# RoverWing-V1_4.net
KiCad netlist of a schematic drawn in EAGLE
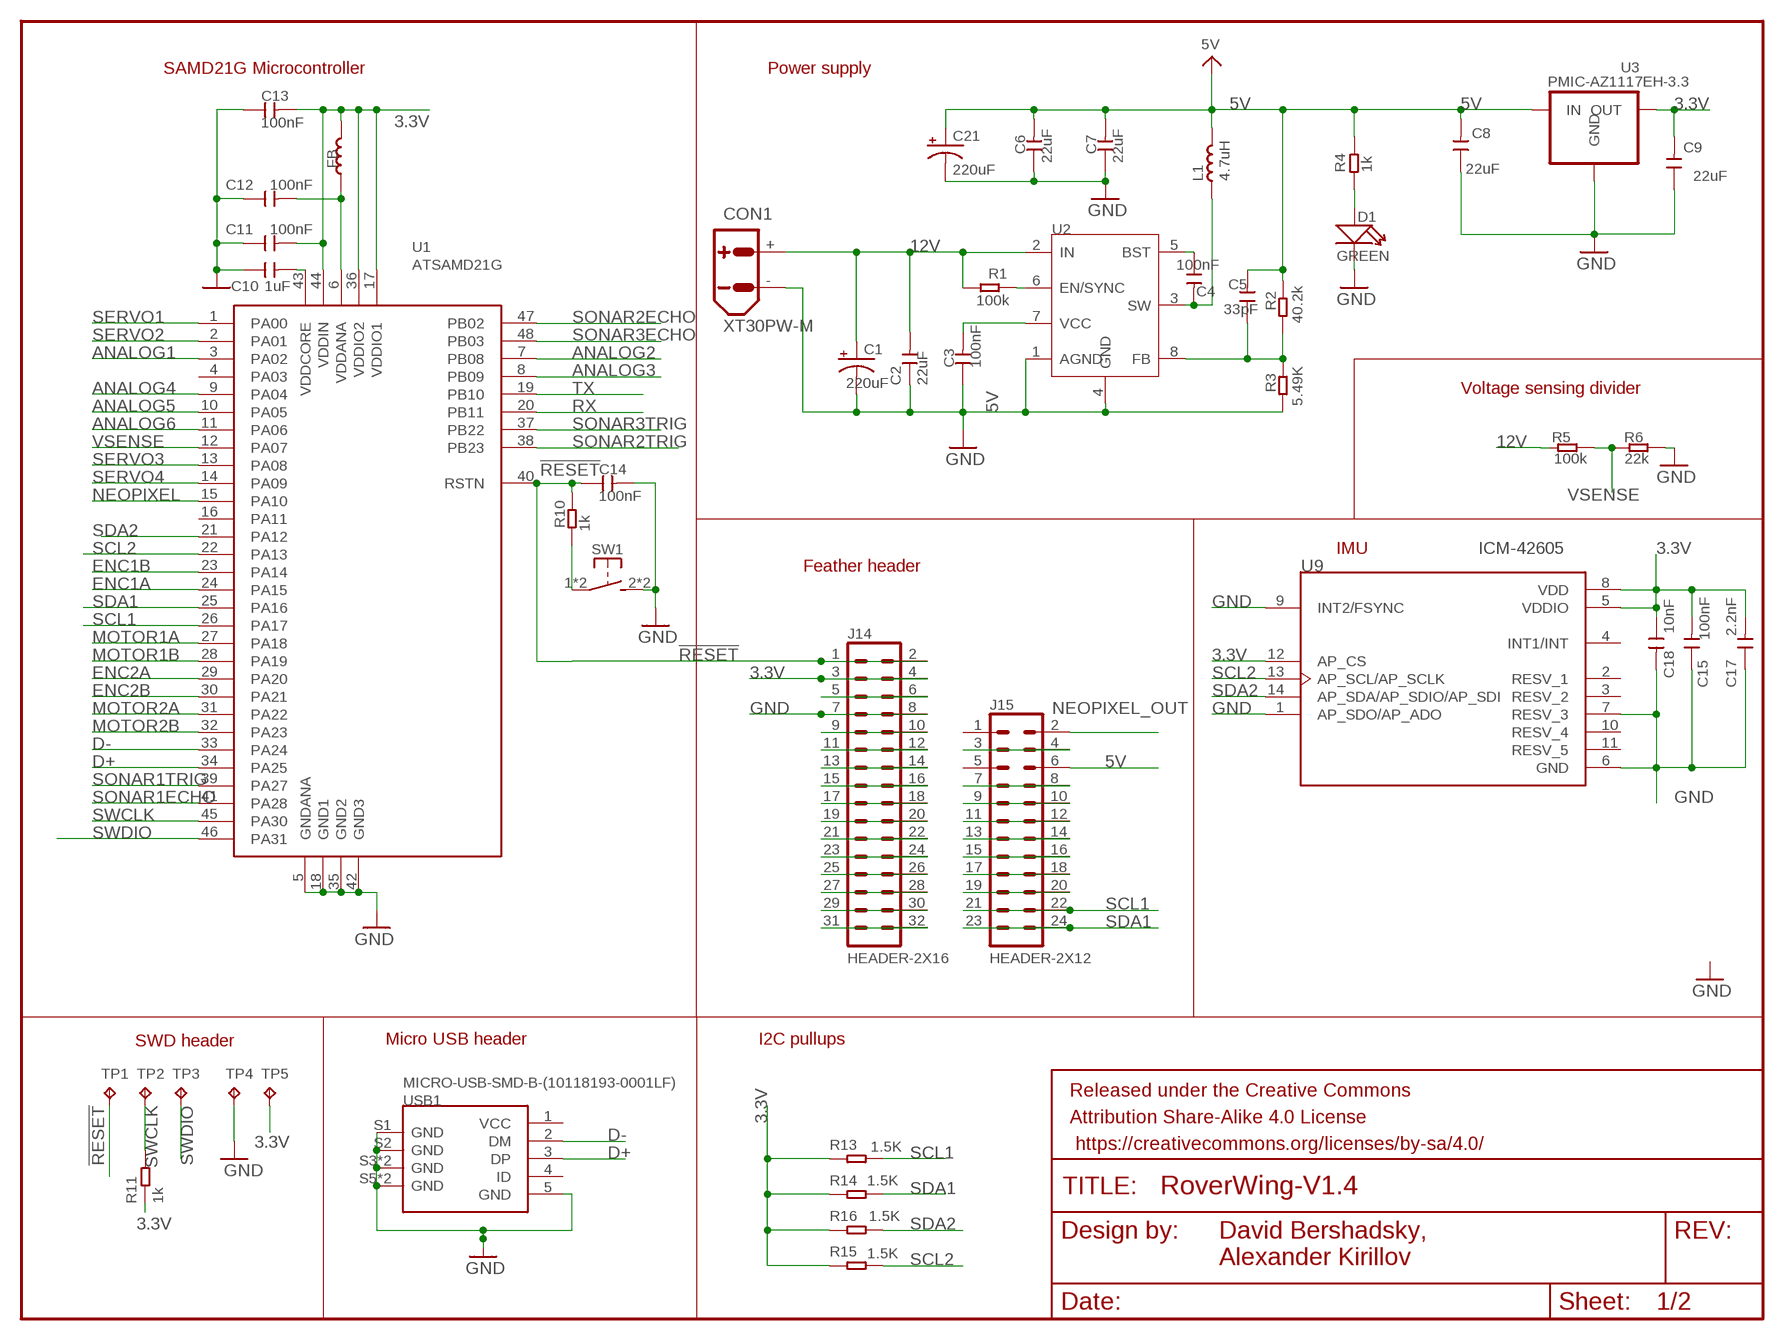
[diagram p0: schematic, sheet 1]
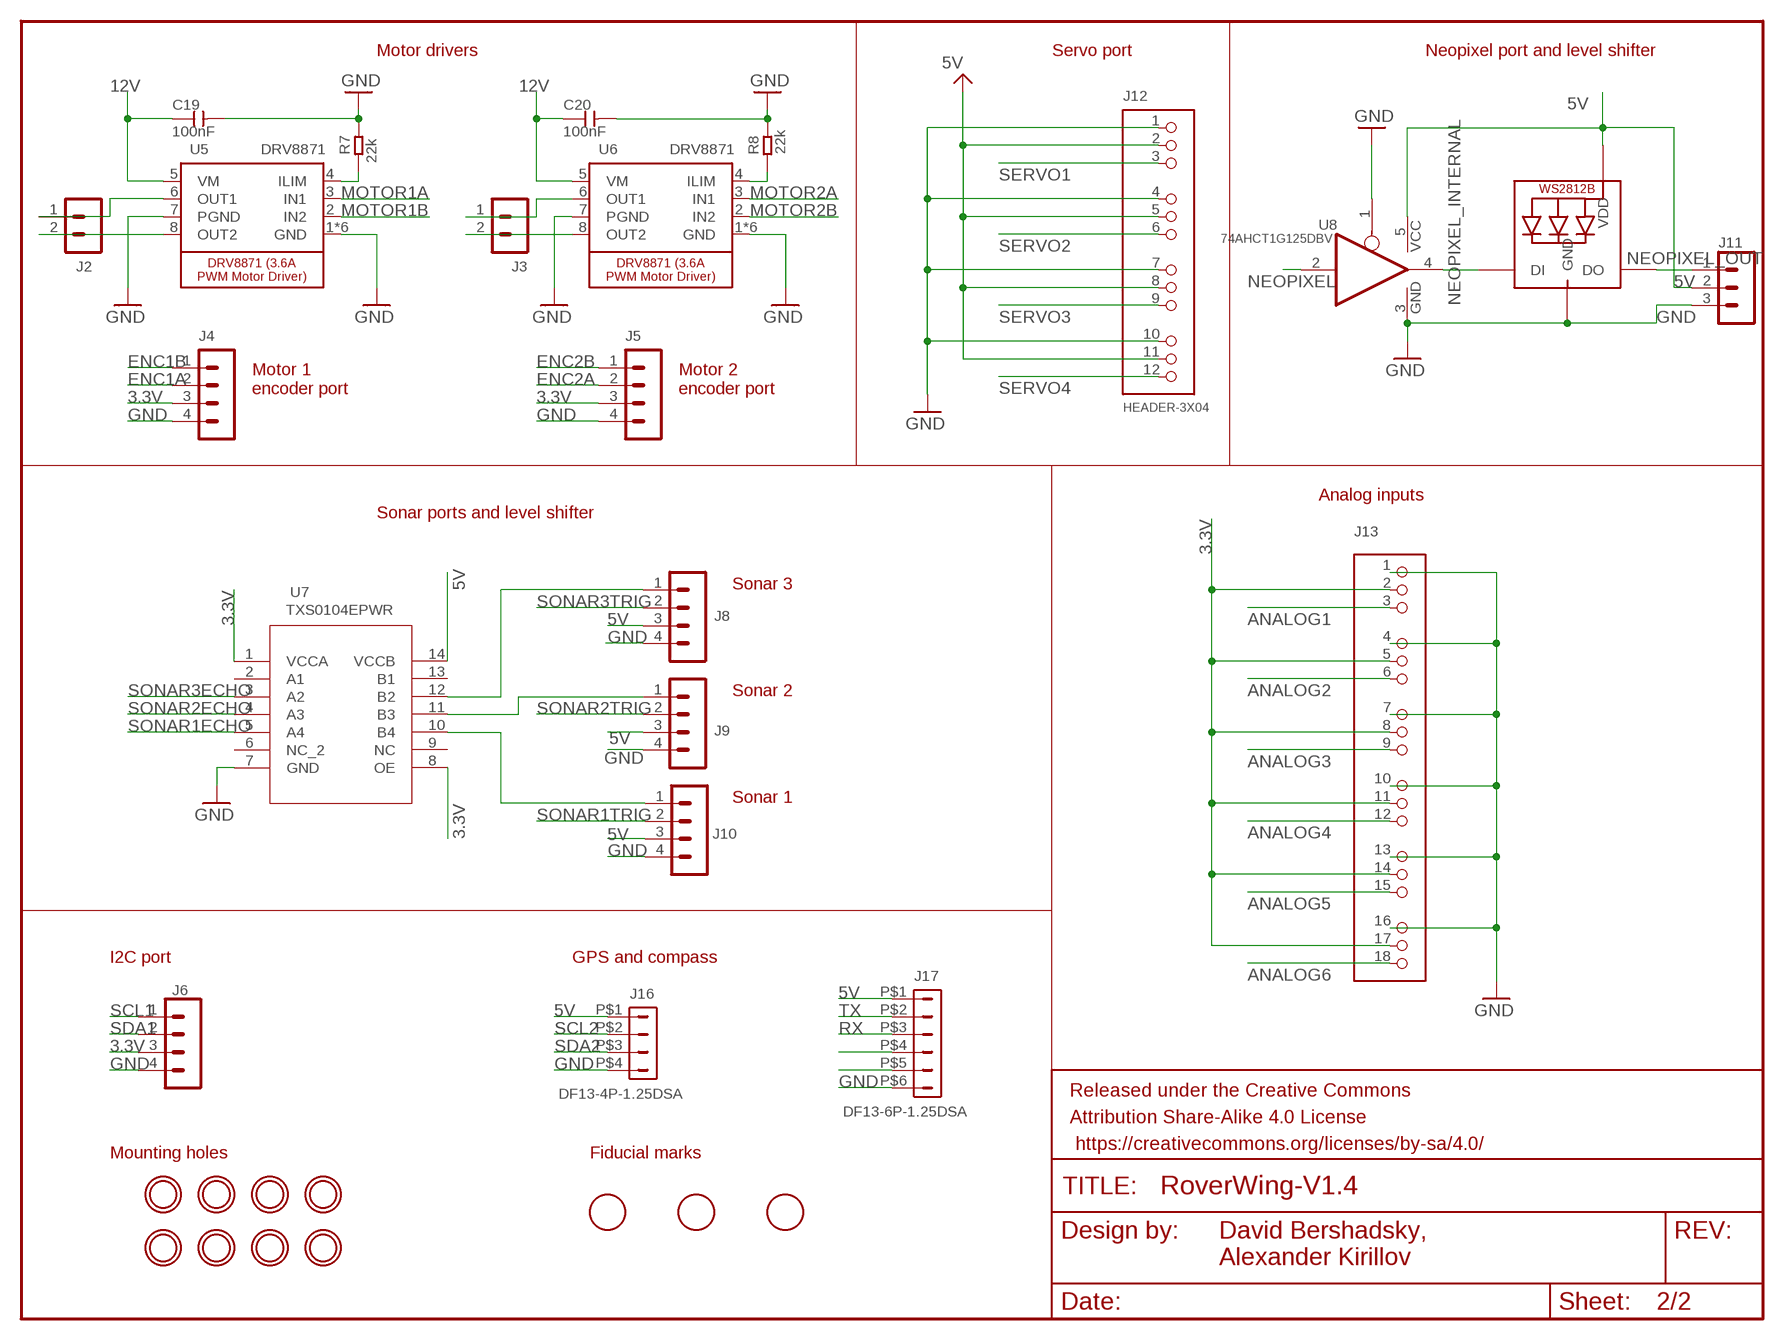
[diagram p1: schematic, sheet 2]

(export (version "E")
  (design (tool "Eeschema 10.0.6"))
  (components
    (comp (ref "C1")
      (value "220uF")
      (footprint "eagle-import:CAP-8X10.5")
      (libsource (lib "eagle-import") (part "CAP-POL-SMD-8X10.5"))
    )
    (comp (ref "C2")
      (value "22uF")
      (footprint "eagle-import:0805")
      (libsource (lib "eagle-import") (part "CAP-CERAMIC-SMD0805"))
    )
    (comp (ref "C3")
      (value "100nF")
      (footprint "eagle-import:0805")
      (libsource (lib "eagle-import") (part "CAP-CERAMIC-SMD0805"))
    )
    (comp (ref "C4")
      (value "100nF")
      (footprint "eagle-import:0805")
      (libsource (lib "eagle-import") (part "CAP-CERAMIC-SMD0805"))
    )
    (comp (ref "C5")
      (value "33pF")
      (footprint "eagle-import:0805")
      (libsource (lib "eagle-import") (part "CAP-CERAMIC-SMD0805"))
    )
    (comp (ref "C6")
      (value "22uF")
      (footprint "eagle-import:0805")
      (libsource (lib "eagle-import") (part "CAP-CERAMIC-SMD0805"))
    )
    (comp (ref "C7")
      (value "22uF")
      (footprint "eagle-import:0805")
      (libsource (lib "eagle-import") (part "CAP-CERAMIC-SMD0805"))
    )
    (comp (ref "C8")
      (value "22uF")
      (footprint "eagle-import:0805")
      (libsource (lib "eagle-import") (part "CAP-CERAMIC-SMD0805"))
    )
    (comp (ref "C9")
      (value "22uF")
      (footprint "eagle-import:0805")
      (libsource (lib "eagle-import") (part "CAP-CERAMIC-SMD0805"))
    )
    (comp (ref "C10")
      (value "1uF")
      (footprint "eagle-import:0805")
      (libsource (lib "eagle-import") (part "CAP-CERAMIC-SMD0805"))
    )
    (comp (ref "C11")
      (value "100nF")
      (footprint "eagle-import:0805")
      (libsource (lib "eagle-import") (part "CAP-CERAMIC-SMD0805"))
    )
    (comp (ref "C12")
      (value "100nF")
      (footprint "eagle-import:0805")
      (libsource (lib "eagle-import") (part "CAP-CERAMIC-SMD0805"))
    )
    (comp (ref "C13")
      (value "100nF")
      (footprint "eagle-import:0805")
      (libsource (lib "eagle-import") (part "CAP-CERAMIC-SMD0805"))
    )
    (comp (ref "C14")
      (value "100nF")
      (footprint "eagle-import:0805")
      (libsource (lib "eagle-import") (part "CAP-CERAMIC-SMD0805"))
    )
    (comp (ref "C15")
      (value "100nF")
      (footprint "eagle-import:0805")
      (libsource (lib "eagle-import") (part "CAP-CERAMIC-SMD0805"))
    )
    (comp (ref "C17")
      (value "2.2nF")
      (footprint "eagle-import:0805")
      (libsource (lib "eagle-import") (part "CAP-CERAMIC-SMD0805"))
    )
    (comp (ref "C18")
      (value "10nF")
      (footprint "eagle-import:0805")
      (libsource (lib "eagle-import") (part "CAP-CERAMIC-SMD0805"))
    )
    (comp (ref "C21")
      (value "220uF")
      (footprint "eagle-import:CAP-6.3X5.4")
      (fields (field (name "PARTNO") "CS1E470M-CRE54 "))
      (libsource (lib "eagle-import") (part "CAP-POL-SMD-6.3X5.4"))
    )
    (comp (ref "CON1")
      (value "XT30PW-M")
      (footprint "eagle-import:XT30PW-M")
      (libsource (lib "eagle-import") (part "XT30PW-M"))
    )
    (comp (ref "D1")
      (value "GREEN")
      (footprint "eagle-import:LED-0805")
      (libsource (lib "eagle-import") (part "SMD-LED-0805"))
    )
    (comp (ref "FB")
      (value "330R-1500MA")
      (footprint "eagle-import:0805")
      (fields (field (name "PARTNO") "BLM21PG331SN1D"))
      (libsource (lib "eagle-import") (part "SMD-FERRITE-BEAD-330R-1500MA(0805)"))
    )
    (comp (ref "FRAME2")
      (value "FRAME-LETTERNO_PACKAGE")
      (footprint "eagle-import:DUMMY")
      (libsource (lib "eagle-import") (part "FRAME-LETTERNO_PACKAGE"))
    )
    (comp (ref "J14")
      (value "HEADER-2X16")
      (footprint "eagle-import:2X16")
      (libsource (lib "eagle-import") (part "HEADER-2X16"))
    )
    (comp (ref "J15")
      (value "HEADER-2X12")
      (footprint "eagle-import:2X12")
      (libsource (lib "eagle-import") (part "HEADER-2X12"))
    )
    (comp (ref "L1")
      (value "4.7uH")
      (footprint "eagle-import:IND_TDK_7.1X6.5")
      (fields (field (name "MANUFACTURER") "TDK") (field (name "PARTNO") "SPM6530T-4R7M "))
      (libsource (lib "eagle-import") (part "IND-TDK-SPM6530T"))
    )
    (comp (ref "R1")
      (value "100k")
      (footprint "eagle-import:0805")
      (libsource (lib "eagle-import") (part "RES-SMD-0805"))
    )
    (comp (ref "R2")
      (value "40.2k")
      (footprint "eagle-import:0805")
      (libsource (lib "eagle-import") (part "RES-SMD-0805"))
    )
    (comp (ref "R3")
      (value "5.49K")
      (footprint "eagle-import:0805")
      (libsource (lib "eagle-import") (part "RES-SMD-0805"))
    )
    (comp (ref "R4")
      (value "1k")
      (footprint "eagle-import:0805")
      (libsource (lib "eagle-import") (part "RES-SMD-0805"))
    )
    (comp (ref "R5")
      (value "100k")
      (footprint "eagle-import:0805")
      (libsource (lib "eagle-import") (part "RES-SMD-0805"))
    )
    (comp (ref "R6")
      (value "22k")
      (footprint "eagle-import:0805")
      (libsource (lib "eagle-import") (part "RES-SMD-0805"))
    )
    (comp (ref "R10")
      (value "1k")
      (footprint "eagle-import:0805")
      (libsource (lib "eagle-import") (part "RES-SMD-0805"))
    )
    (comp (ref "R11")
      (value "1k")
      (footprint "eagle-import:0805")
      (libsource (lib "eagle-import") (part "RES-SMD-0805"))
    )
    (comp (ref "R13")
      (value "1.5K")
      (footprint "eagle-import:R0603")
      (fields (field (name "MPN") "RC0603FR-071K8L"))
      (libsource (lib "eagle-import") (part "SMD-RES-1.8K-1%-1/10W(0603)"))
    )
    (comp (ref "R14")
      (value "1.5K")
      (footprint "eagle-import:R0603")
      (fields (field (name "MPN") "RC0603FR-071K8L"))
      (libsource (lib "eagle-import") (part "SMD-RES-1.8K-1%-1/10W(0603)"))
    )
    (comp (ref "R15")
      (value "1.5K")
      (footprint "eagle-import:R0603")
      (fields (field (name "MPN") "RC0603FR-071K8L"))
      (libsource (lib "eagle-import") (part "SMD-RES-1.8K-1%-1/10W(0603)"))
    )
    (comp (ref "R16")
      (value "1.5K")
      (footprint "eagle-import:R0603")
      (fields (field (name "MPN") "RC0603FR-071K8L"))
      (libsource (lib "eagle-import") (part "SMD-RES-1.8K-1%-1/10W(0603)"))
    )
    (comp (ref "SW1")
      (value "SW-TACTILE-4.5X4.5_SMD")
      (footprint "eagle-import:TL3305")
      (fields (field (name "MANUFACTURER") "BRIGHT") (field (name "PARTNO") "TSA453G38-250 "))
      (libsource (lib "eagle-import") (part "SW-TACTILE-4.5X4.5_SMD"))
    )
    (comp (ref "TP1")
      (value "TPTP15R")
      (footprint "eagle-import:TP15R")
      (libsource (lib "eagle-import") (part "TPTP15R"))
    )
    (comp (ref "TP2")
      (value "TPTP15R")
      (footprint "eagle-import:TP15R")
      (libsource (lib "eagle-import") (part "TPTP15R"))
    )
    (comp (ref "TP3")
      (value "TPTP15R")
      (footprint "eagle-import:TP15R")
      (libsource (lib "eagle-import") (part "TPTP15R"))
    )
    (comp (ref "TP4")
      (value "TPTP15R")
      (footprint "eagle-import:TP15R")
      (libsource (lib "eagle-import") (part "TPTP15R"))
    )
    (comp (ref "TP5")
      (value "TPTP15R")
      (footprint "eagle-import:TP15R")
      (libsource (lib "eagle-import") (part "TPTP15R"))
    )
    (comp (ref "U1")
      (value "ATSAMD21G")
      (footprint "eagle-import:TQFP-48-EDITED")
      (fields (field (name "MANUFACTURER") "Microchip Technology") (field (name "PARTNO") "ATSAMD21G18A-AU"))
      (libsource (lib "eagle-import") (part "ATSAMD21G"))
    )
    (comp (ref "U2")
      (value "MP2225")
      (footprint "eagle-import:SOT-23-8")
      (fields (field (name "MANUFACTURER") "Monolithic Power Systems") (field (name "PARTNO") "MP2225GJ"))
      (libsource (lib "eagle-import") (part "PMIC-MP2225"))
    )
    (comp (ref "U3")
      (value "PMIC-AZ1117EH-3.3")
      (footprint "eagle-import:SOT223")
      (fields (field (name "PARTNO") "AZ1117EH-3.3TRG1"))
      (libsource (lib "eagle-import") (part "PMIC-AZ1117EH-3.3"))
    )
    (comp (ref "U9")
      (value "ICM-42605")
      (footprint "eagle-import:PQFN50P300X250X97-14N")
      (fields (field (name "DIGI-KEY_PART_NUMBER") "1428-1152-1-ND") (field (name "MF") "TDK InvenSense"))
      (libsource (lib "eagle-import") (part "ICM-42605"))
    )
    (comp (ref "USB1")
      (value "MICRO-USB-SMD-B-(10118193-0001LF)")
      (footprint "eagle-import:MICRO-USB5+6P-SMD-0.65-B")
      (fields (field (name "MANUFACTURER") "Amphenol ICC") (field (name "PARTNO") "10118193-0001LF"))
      (libsource (lib "eagle-import") (part "MICRO-USB-SMD-B-(10118193-0001LF)"))
    )
    (comp (ref "C19")
      (value "100nF")
      (footprint "eagle-import:0805")
      (libsource (lib "eagle-import") (part "CAP-CERAMIC-SMD0805"))
    )
    (comp (ref "C20")
      (value "100nF")
      (footprint "eagle-import:0805")
      (libsource (lib "eagle-import") (part "CAP-CERAMIC-SMD0805"))
    )
    (comp (ref "D2")
      (value "WS2812B3535")
      (footprint "eagle-import:LED3535")
      (fields (field (name "MANUFACTURER") "Worldsemi") (field (name "PARTNO") "WS2812B-3535 "))
      (libsource (lib "eagle-import") (part "WS2812B3535"))
    )
    (comp (ref "FRAME1")
      (value "FRAME-LETTERNO_PACKAGE")
      (footprint "eagle-import:DUMMY")
      (libsource (lib "eagle-import") (part "FRAME-LETTERNO_PACKAGE"))
    )
    (comp (ref "J2")
      (value "HEADER-VH")
      (footprint "eagle-import:B2P-VH")
      (fields (field (name "PARTNO") "B2P-VH(LF)(SN)  "))
      (libsource (lib "eagle-import") (part "HEADER-VH"))
    )
    (comp (ref "J3")
      (value "HEADER-VH")
      (footprint "eagle-import:B2P-VH")
      (fields (field (name "PARTNO") "B2P-VH(LF)(SN)  "))
      (libsource (lib "eagle-import") (part "HEADER-VH"))
    )
    (comp (ref "J4")
      (value "HEADER-PH-4P")
      (footprint "eagle-import:B4B-PH-K")
      (fields (field (name "PARTNO") "B4B-PH-K-S(LF)(SN)"))
      (libsource (lib "eagle-import") (part "HEADER-PH-4P"))
    )
    (comp (ref "J5")
      (value "HEADER-PH-4P")
      (footprint "eagle-import:B4B-PH-K")
      (fields (field (name "PARTNO") "B4B-PH-K-S(LF)(SN)"))
      (libsource (lib "eagle-import") (part "HEADER-PH-4P"))
    )
    (comp (ref "J6")
      (value "HEADER-PH-4P")
      (footprint "eagle-import:B4B-PH-K")
      (fields (field (name "PARTNO") "B4B-PH-K-S(LF)(SN)"))
      (libsource (lib "eagle-import") (part "HEADER-PH-4P"))
    )
    (comp (ref "J8")
      (value "HEADER-PH-4P")
      (footprint "eagle-import:B4B-PH-K")
      (fields (field (name "PARTNO") "B4B-PH-K-S(LF)(SN)"))
      (libsource (lib "eagle-import") (part "HEADER-PH-4P"))
    )
    (comp (ref "J9")
      (value "HEADER-PH-4P")
      (footprint "eagle-import:B4B-PH-K")
      (fields (field (name "PARTNO") "B4B-PH-K-S(LF)(SN)"))
      (libsource (lib "eagle-import") (part "HEADER-PH-4P"))
    )
    (comp (ref "J10")
      (value "HEADER-PH-4P")
      (footprint "eagle-import:B4B-PH-K")
      (fields (field (name "PARTNO") "B4B-PH-K-S(LF)(SN)"))
      (libsource (lib "eagle-import") (part "HEADER-PH-4P"))
    )
    (comp (ref "J11")
      (value "HEADER-PH-3P")
      (footprint "eagle-import:B3B-PH-K")
      (fields (field (name "PARTNO") "B3B-PH-K-S(LF)(SN)"))
      (libsource (lib "eagle-import") (part "HEADER-PH-3P"))
    )
    (comp (ref "J12")
      (value "HEADER-3X04")
      (footprint "eagle-import:3X04")
      (libsource (lib "eagle-import") (part "HEADER-3X04"))
    )
    (comp (ref "J13")
      (value "HEADER-3X06\"")
      (footprint "eagle-import:3X06")
      (libsource (lib "eagle-import") (part "HEADER-3X06{dblquote}"))
    )
    (comp (ref "J16")
      (value "DF13-4P-1.25DSA")
      (footprint "eagle-import:DF13-4P-1.25DSA")
      (libsource (lib "eagle-import") (part "DF13-4P-1.25DSA"))
    )
    (comp (ref "J17")
      (value "DF13-6P-1.25DSA")
      (footprint "eagle-import:DF13-6P-1.25DSA")
      (libsource (lib "eagle-import") (part "DF13-6P-1.25DSA"))
    )
    (comp (ref "R7")
      (value "22k")
      (footprint "eagle-import:0805")
      (libsource (lib "eagle-import") (part "RES-SMD-0805"))
    )
    (comp (ref "R8")
      (value "22k")
      (footprint "eagle-import:0805")
      (libsource (lib "eagle-import") (part "RES-SMD-0805"))
    )
    (comp (ref "U$3")
      (value "MOUNTINGHOLE3.0_NPH")
      (footprint "eagle-import:MOUNTINGHOLE_3.0_NPH")
      (libsource (lib "eagle-import") (part "MOUNTINGHOLE3.0_NPH"))
    )
    (comp (ref "U$4")
      (value "MOUNTINGHOLE3.0_NPH")
      (footprint "eagle-import:MOUNTINGHOLE_3.0_NPH")
      (libsource (lib "eagle-import") (part "MOUNTINGHOLE3.0_NPH"))
    )
    (comp (ref "U$11")
      (value "FIDUCIAL")
      (footprint "eagle-import:FIDUCIAL_1MM")
      (libsource (lib "eagle-import") (part "FIDUCIAL"))
    )
    (comp (ref "U$13")
      (value "FIDUCIAL")
      (footprint "eagle-import:FIDUCIAL_1MM")
      (libsource (lib "eagle-import") (part "FIDUCIAL"))
    )
    (comp (ref "U$14")
      (value "MOUNTINGHOLE3.0_NPH")
      (footprint "eagle-import:MOUNTINGHOLE_3.0_NPH")
      (libsource (lib "eagle-import") (part "MOUNTINGHOLE3.0_NPH"))
    )
    (comp (ref "U$15")
      (value "MOUNTINGHOLE3.0_NPH")
      (footprint "eagle-import:MOUNTINGHOLE_3.0_NPH")
      (libsource (lib "eagle-import") (part "MOUNTINGHOLE3.0_NPH"))
    )
    (comp (ref "U$17")
      (value "FIDUCIAL")
      (footprint "eagle-import:FIDUCIAL_1MM")
      (libsource (lib "eagle-import") (part "FIDUCIAL"))
    )
    (comp (ref "U$24")
      (value "MOUNTINGHOLE3.0_NPH")
      (footprint "eagle-import:MOUNTINGHOLE_3.0_NPH")
      (libsource (lib "eagle-import") (part "MOUNTINGHOLE3.0_NPH"))
    )
    (comp (ref "U$25")
      (value "MOUNTINGHOLE3.0_NPH")
      (footprint "eagle-import:MOUNTINGHOLE_3.0_NPH")
      (libsource (lib "eagle-import") (part "MOUNTINGHOLE3.0_NPH"))
    )
    (comp (ref "U$26")
      (value "MOUNTINGHOLE3.0_NPH")
      (footprint "eagle-import:MOUNTINGHOLE_3.0_NPH")
      (libsource (lib "eagle-import") (part "MOUNTINGHOLE3.0_NPH"))
    )
    (comp (ref "U$27")
      (value "MOUNTINGHOLE3.0_NPH")
      (footprint "eagle-import:MOUNTINGHOLE_3.0_NPH")
      (libsource (lib "eagle-import") (part "MOUNTINGHOLE3.0_NPH"))
    )
    (comp (ref "U5")
      (value "DRV8871")
      (footprint "eagle-import:HSOP8")
      (fields (field (name "MANUFACTURER") "TEXAS INSTRUMENTS") (field (name "PARTNO") "DRV8871DDAR"))
      (libsource (lib "eagle-import") (part "DRV8871"))
    )
    (comp (ref "U6")
      (value "DRV8871")
      (footprint "eagle-import:HSOP8")
      (fields (field (name "MANUFACTURER") "TEXAS INSTRUMENTS") (field (name "PARTNO") "DRV8871DDAR"))
      (libsource (lib "eagle-import") (part "DRV8871"))
    )
    (comp (ref "U7")
      (value "TXS0104EPWR")
      (footprint "eagle-import:PW14")
      (fields (field (name "MANUFACTURER") "Texas Instruments"))
      (libsource (lib "eagle-import") (part "TXS0104EPWR"))
    )
    (comp (ref "U8")
      (value "74AHCT1G125DBV")
      (footprint "eagle-import:SOT23-5")
      (fields (field (name "PARTNO") "SN74AHCT1G125DBVR"))
      (libsource (lib "eagle-import") (part "741G125DBVAHCT"))
    )
  )
  (nets
    (net (code "1") (name "3.3V") (class "Default")
      (node (ref "C11") (pin "2") (pinfunction "2_2") (pintype "passive"))
      (node (ref "C13") (pin "2") (pinfunction "2_2") (pintype "passive"))
      (node (ref "C15") (pin "2") (pinfunction "2_2") (pintype "passive"))
      (node (ref "C17") (pin "2") (pinfunction "2_2") (pintype "passive"))
      (node (ref "C18") (pin "1") (pinfunction "1_1") (pintype "passive"))
      (node (ref "C9") (pin "2") (pinfunction "2_2") (pintype "passive"))
      (node (ref "FB") (pin "2") (pinfunction "2_2") (pintype "passive"))
      (node (ref "J13") (pin "11") (pinfunction "11_11") (pintype "passive"))
      (node (ref "J13") (pin "14") (pinfunction "14_14") (pintype "passive"))
      (node (ref "J13") (pin "17") (pinfunction "17_17") (pintype "passive"))
      (node (ref "J13") (pin "2") (pinfunction "2_2") (pintype "passive"))
      (node (ref "J13") (pin "5") (pinfunction "5_5") (pintype "passive"))
      (node (ref "J13") (pin "8") (pinfunction "8_8") (pintype "passive"))
      (node (ref "J14") (pin "3") (pinfunction "3_3") (pintype "passive"))
      (node (ref "J14") (pin "4") (pinfunction "4_4") (pintype "passive"))
      (node (ref "J4") (pin "3") (pinfunction "3_3") (pintype "passive"))
      (node (ref "J5") (pin "3") (pinfunction "3_3") (pintype "passive"))
      (node (ref "J6") (pin "3") (pinfunction "3_3") (pintype "passive"))
      (node (ref "R11") (pin "1") (pinfunction "1_1") (pintype "passive"))
      (node (ref "R13") (pin "1") (pinfunction "1_1") (pintype "passive"))
      (node (ref "R14") (pin "1") (pinfunction "1_1") (pintype "passive"))
      (node (ref "R15") (pin "1") (pinfunction "1_1") (pintype "passive"))
      (node (ref "R16") (pin "1") (pinfunction "1_1") (pintype "passive"))
      (node (ref "TP5") (pin "TP") (pinfunction "TP_TP") (pintype "input"))
      (node (ref "U1") (pin "17") (pinfunction "VDDIO1_17") (pintype "power_in"))
      (node (ref "U1") (pin "36") (pinfunction "VDDIO2_36") (pintype "power_in"))
      (node (ref "U1") (pin "44") (pinfunction "VDDIN_44") (pintype "power_in"))
      (node (ref "U3") (pin "2") (pinfunction "OUT_2") (pintype "output"))
      (node (ref "U3") (pin "4") (pinfunction "OUT_4") (pintype "output"))
      (node (ref "U7") (pin "1") (pinfunction "VCCA_1") (pintype "power_in"))
      (node (ref "U7") (pin "8") (pinfunction "OE_8") (pintype "output"))
      (node (ref "U9") (pin "12") (pinfunction "AP_CS_12") (pintype "input"))
      (node (ref "U9") (pin "5") (pinfunction "VDDIO_5") (pintype "power_in"))
      (node (ref "U9") (pin "8") (pinfunction "VDD_8") (pintype "power_in"))
    )
    (net (code "2") (name "5V") (class "Default")
      (node (ref "C21") (pin "+") (pinfunction "+_+") (pintype "passive"))
      (node (ref "C5") (pin "2") (pinfunction "2_2") (pintype "passive"))
      (node (ref "C6") (pin "2") (pinfunction "2_2") (pintype "passive"))
      (node (ref "C7") (pin "2") (pinfunction "2_2") (pintype "passive"))
      (node (ref "C8") (pin "2") (pinfunction "2_2") (pintype "passive"))
      (node (ref "D2") (pin "3") (pinfunction "VDD_3") (pintype "power_in"))
      (node (ref "J10") (pin "3") (pinfunction "3_3") (pintype "passive"))
      (node (ref "J11") (pin "2") (pinfunction "2_2") (pintype "passive"))
      (node (ref "J12") (pin "11") (pinfunction "11_11") (pintype "passive"))
      (node (ref "J12") (pin "2") (pinfunction "2_2") (pintype "passive"))
      (node (ref "J12") (pin "5") (pinfunction "5_5") (pintype "passive"))
      (node (ref "J12") (pin "8") (pinfunction "8_8") (pintype "passive"))
      (node (ref "J15") (pin "6") (pinfunction "6_6") (pintype "passive"))
      (node (ref "J16") (pin "P$1") (pinfunction "1_P$1") (pintype "passive"))
      (node (ref "J17") (pin "P$1") (pinfunction "1_P$1") (pintype "passive"))
      (node (ref "J8") (pin "3") (pinfunction "3_3") (pintype "passive"))
      (node (ref "J9") (pin "3") (pinfunction "3_3") (pintype "passive"))
      (node (ref "L1") (pin "2") (pinfunction "2_2") (pintype "passive"))
      (node (ref "R2") (pin "1") (pinfunction "1_1") (pintype "passive"))
      (node (ref "R4") (pin "2") (pinfunction "2_2") (pintype "passive"))
      (node (ref "U3") (pin "3") (pinfunction "IN_3") (pintype "input"))
      (node (ref "U7") (pin "14") (pinfunction "VCCB_14") (pintype "power_in"))
      (node (ref "U8") (pin "5") (pinfunction "VCC_5") (pintype "power_in"))
    )
    (net (code "3") (name "12V") (class "Default")
      (node (ref "C1") (pin "+") (pinfunction "+_+") (pintype "passive"))
      (node (ref "C19") (pin "1") (pinfunction "1_1") (pintype "passive"))
      (node (ref "C2") (pin "2") (pinfunction "2_2") (pintype "passive"))
      (node (ref "C20") (pin "1") (pinfunction "1_1") (pintype "passive"))
      (node (ref "CON1") (pin "+") (pinfunction "+_+") (pintype "power_in"))
      (node (ref "R1") (pin "2") (pinfunction "2_2") (pintype "passive"))
      (node (ref "R5") (pin "2") (pinfunction "2_2") (pintype "passive"))
      (node (ref "U2") (pin "2") (pinfunction "IN_2") (pintype "bidirectional"))
      (node (ref "U5") (pin "5") (pinfunction "VM_5") (pintype "power_in"))
      (node (ref "U6") (pin "5") (pinfunction "VM_5") (pintype "power_in"))
    )
    (net (code "4") (name "ANALOG1") (class "Default")
      (node (ref "J13") (pin "3") (pinfunction "3_3") (pintype "passive"))
      (node (ref "U1") (pin "3") (pinfunction "PA02_3") (pintype "bidirectional"))
    )
    (net (code "5") (name "ANALOG2") (class "Default")
      (node (ref "J13") (pin "6") (pinfunction "6_6") (pintype "passive"))
      (node (ref "U1") (pin "7") (pinfunction "PB08_7") (pintype "bidirectional"))
    )
    (net (code "6") (name "ANALOG3") (class "Default")
      (node (ref "J13") (pin "9") (pinfunction "9_9") (pintype "passive"))
      (node (ref "U1") (pin "8") (pinfunction "PB09_8") (pintype "bidirectional"))
    )
    (net (code "7") (name "ANALOG4") (class "Default")
      (node (ref "J13") (pin "12") (pinfunction "12_12") (pintype "passive"))
      (node (ref "U1") (pin "9") (pinfunction "PA04_9") (pintype "bidirectional"))
    )
    (net (code "8") (name "ANALOG5") (class "Default")
      (node (ref "J13") (pin "15") (pinfunction "15_15") (pintype "passive"))
      (node (ref "U1") (pin "10") (pinfunction "PA05_10") (pintype "bidirectional"))
    )
    (net (code "9") (name "ANALOG6") (class "Default")
      (node (ref "J13") (pin "18") (pinfunction "18_18") (pintype "passive"))
      (node (ref "U1") (pin "11") (pinfunction "PA06_11") (pintype "bidirectional"))
    )
    (net (code "10") (name "D+") (class "Default")
      (node (ref "U1") (pin "34") (pinfunction "PA25_34") (pintype "bidirectional"))
      (node (ref "USB1") (pin "3") (pinfunction "DP_3") (pintype "bidirectional"))
    )
    (net (code "11") (name "D-") (class "Default")
      (node (ref "U1") (pin "33") (pinfunction "PA24_33") (pintype "bidirectional"))
      (node (ref "USB1") (pin "2") (pinfunction "DM_2") (pintype "bidirectional"))
    )
    (net (code "12") (name "ENC1A") (class "Default")
      (node (ref "J4") (pin "2") (pinfunction "2_2") (pintype "passive"))
      (node (ref "U1") (pin "24") (pinfunction "PA15_24") (pintype "bidirectional"))
    )
    (net (code "13") (name "ENC1B") (class "Default")
      (node (ref "J4") (pin "1") (pinfunction "1_1") (pintype "passive"))
      (node (ref "U1") (pin "23") (pinfunction "PA14_23") (pintype "bidirectional"))
    )
    (net (code "14") (name "ENC2A") (class "Default")
      (node (ref "J5") (pin "2") (pinfunction "2_2") (pintype "passive"))
      (node (ref "U1") (pin "29") (pinfunction "PA20_29") (pintype "bidirectional"))
    )
    (net (code "15") (name "ENC2B") (class "Default")
      (node (ref "J5") (pin "1") (pinfunction "1_1") (pintype "passive"))
      (node (ref "U1") (pin "30") (pinfunction "PA21_30") (pintype "bidirectional"))
    )
    (net (code "16") (name "GND") (class "Default")
      (node (ref "C1") (pin "-") (pinfunction "-_-") (pintype "passive"))
      (node (ref "C10") (pin "1") (pinfunction "1_1") (pintype "passive"))
      (node (ref "C11") (pin "1") (pinfunction "1_1") (pintype "passive"))
      (node (ref "C12") (pin "1") (pinfunction "1_1") (pintype "passive"))
      (node (ref "C13") (pin "1") (pinfunction "1_1") (pintype "passive"))
      (node (ref "C14") (pin "2") (pinfunction "2_2") (pintype "passive"))
      (node (ref "C15") (pin "1") (pinfunction "1_1") (pintype "passive"))
      (node (ref "C17") (pin "1") (pinfunction "1_1") (pintype "passive"))
      (node (ref "C18") (pin "2") (pinfunction "2_2") (pintype "passive"))
      (node (ref "C19") (pin "2") (pinfunction "2_2") (pintype "passive"))
      (node (ref "C2") (pin "1") (pinfunction "1_1") (pintype "passive"))
      (node (ref "C20") (pin "2") (pinfunction "2_2") (pintype "passive"))
      (node (ref "C21") (pin "-") (pinfunction "-_-") (pintype "passive"))
      (node (ref "C3") (pin "1") (pinfunction "1_1") (pintype "passive"))
      (node (ref "C6") (pin "1") (pinfunction "1_1") (pintype "passive"))
      (node (ref "C7") (pin "1") (pinfunction "1_1") (pintype "passive"))
      (node (ref "C8") (pin "1") (pinfunction "1_1") (pintype "passive"))
      (node (ref "C9") (pin "1") (pinfunction "1_1") (pintype "passive"))
      (node (ref "CON1") (pin "-") (pinfunction "-_-") (pintype "power_in"))
      (node (ref "D1") (pin "-") (pinfunction "-_-") (pintype "passive"))
      (node (ref "D2") (pin "1") (pinfunction "GND_1") (pintype "power_in"))
      (node (ref "J10") (pin "4") (pinfunction "4_4") (pintype "passive"))
      (node (ref "J11") (pin "3") (pinfunction "3_3") (pintype "passive"))
      (node (ref "J12") (pin "1") (pinfunction "1_1") (pintype "passive"))
      (node (ref "J12") (pin "10") (pinfunction "10_10") (pintype "passive"))
      (node (ref "J12") (pin "4") (pinfunction "4_4") (pintype "passive"))
      (node (ref "J12") (pin "7") (pinfunction "7_7") (pintype "passive"))
      (node (ref "J13") (pin "1") (pinfunction "1_1") (pintype "passive"))
      (node (ref "J13") (pin "10") (pinfunction "10_10") (pintype "passive"))
      (node (ref "J13") (pin "13") (pinfunction "13_13") (pintype "passive"))
      (node (ref "J13") (pin "16") (pinfunction "16_16") (pintype "passive"))
      (node (ref "J13") (pin "4") (pinfunction "4_4") (pintype "passive"))
      (node (ref "J13") (pin "7") (pinfunction "7_7") (pintype "passive"))
      (node (ref "J14") (pin "7") (pinfunction "7_7") (pintype "passive"))
      (node (ref "J14") (pin "8") (pinfunction "8_8") (pintype "passive"))
      (node (ref "J16") (pin "P$4") (pinfunction "4_P$4") (pintype "passive"))
      (node (ref "J17") (pin "P$6") (pinfunction "6_P$6") (pintype "passive"))
      (node (ref "J4") (pin "4") (pinfunction "4_4") (pintype "passive"))
      (node (ref "J5") (pin "4") (pinfunction "4_4") (pintype "passive"))
      (node (ref "J6") (pin "4") (pinfunction "4_4") (pintype "passive"))
      (node (ref "J8") (pin "4") (pinfunction "4_4") (pintype "passive"))
      (node (ref "J9") (pin "4") (pinfunction "4_4") (pintype "passive"))
      (node (ref "R3") (pin "2") (pinfunction "2_2") (pintype "passive"))
      (node (ref "R6") (pin "2") (pinfunction "2_2") (pintype "passive"))
      (node (ref "R7") (pin "2") (pinfunction "2_2") (pintype "passive"))
      (node (ref "R8") (pin "2") (pinfunction "2_2") (pintype "passive"))
      (node (ref "SW1") (pin "2") (pinfunction "S1_2") (pintype "passive"))
      (node (ref "SW1") (pin "3") (pinfunction "S1_3") (pintype "passive"))
      (node (ref "TP4") (pin "TP") (pinfunction "TP_TP") (pintype "input"))
      (node (ref "U1") (pin "18") (pinfunction "GND1_18") (pintype "power_in"))
      (node (ref "U1") (pin "35") (pinfunction "GND2_35") (pintype "power_in"))
      (node (ref "U1") (pin "42") (pinfunction "GND3_42") (pintype "power_in"))
      (node (ref "U1") (pin "5") (pinfunction "GNDANA_5") (pintype "power_in"))
      (node (ref "U2") (pin "1") (pinfunction "AGND_1") (pintype "bidirectional"))
      (node (ref "U2") (pin "4") (pinfunction "GND_4") (pintype "bidirectional"))
      (node (ref "U3") (pin "1") (pinfunction "GND_1") (pintype "power_in"))
      (node (ref "U5") (pin "1") (pinfunction "GND_1") (pintype "power_in"))
      (node (ref "U5") (pin "7") (pinfunction "PGND_7") (pintype "power_in"))
      (node (ref "U5") (pin "GND") (pinfunction "GND_GND") (pintype "power_in"))
      (node (ref "U5") (pin "P$1") (pinfunction "GND_P$1") (pintype "power_in"))
      (node (ref "U5") (pin "P$2") (pinfunction "GND_P$2") (pintype "power_in"))
      (node (ref "U5") (pin "P$3") (pinfunction "GND_P$3") (pintype "power_in"))
      (node (ref "U5") (pin "P$4") (pinfunction "GND_P$4") (pintype "power_in"))
      (node (ref "U6") (pin "1") (pinfunction "GND_1") (pintype "power_in"))
      (node (ref "U6") (pin "7") (pinfunction "PGND_7") (pintype "power_in"))
      (node (ref "U6") (pin "GND") (pinfunction "GND_GND") (pintype "power_in"))
      (node (ref "U6") (pin "P$1") (pinfunction "GND_P$1") (pintype "power_in"))
      (node (ref "U6") (pin "P$2") (pinfunction "GND_P$2") (pintype "power_in"))
      (node (ref "U6") (pin "P$3") (pinfunction "GND_P$3") (pintype "power_in"))
      (node (ref "U6") (pin "P$4") (pinfunction "GND_P$4") (pintype "power_in"))
      (node (ref "U7") (pin "7") (pinfunction "GND_7") (pintype "power_in"))
      (node (ref "U8") (pin "1") (pinfunction "OE_1") (pintype "input"))
      (node (ref "U8") (pin "3") (pinfunction "GND_3") (pintype "power_in"))
      (node (ref "U9") (pin "1") (pinfunction "AP_SDO/AP_ADO_1") (pintype "output"))
      (node (ref "U9") (pin "6") (pinfunction "GND_6") (pintype "power_in"))
      (node (ref "U9") (pin "7") (pinfunction "RESV_3_7") (pintype "bidirectional"))
      (node (ref "U9") (pin "9") (pinfunction "INT2/FSYNC_9") (pintype "bidirectional"))
      (node (ref "USB1") (pin "5") (pinfunction "GND_5") (pintype "bidirectional"))
      (node (ref "USB1") (pin "S1") (pinfunction "GND_S1") (pintype "bidirectional"))
      (node (ref "USB1") (pin "S2") (pinfunction "GND_S2") (pintype "bidirectional"))
      (node (ref "USB1") (pin "S3") (pinfunction "GND_S3") (pintype "bidirectional"))
      (node (ref "USB1") (pin "S4") (pinfunction "GND_S4") (pintype "bidirectional"))
      (node (ref "USB1") (pin "S5") (pinfunction "GND_S5") (pintype "bidirectional"))
      (node (ref "USB1") (pin "S6") (pinfunction "GND_S6") (pintype "bidirectional"))
    )
    (net (code "17") (name "MOTOR1A") (class "Default")
      (node (ref "U1") (pin "27") (pinfunction "PA18_27") (pintype "bidirectional"))
      (node (ref "U5") (pin "3") (pinfunction "IN1_3") (pintype "input"))
    )
    (net (code "18") (name "MOTOR1B") (class "Default")
      (node (ref "U1") (pin "28") (pinfunction "PA19_28") (pintype "bidirectional"))
      (node (ref "U5") (pin "2") (pinfunction "IN2_2") (pintype "input"))
    )
    (net (code "19") (name "MOTOR2A") (class "Default")
      (node (ref "U1") (pin "31") (pinfunction "PA22_31") (pintype "bidirectional"))
      (node (ref "U6") (pin "3") (pinfunction "IN1_3") (pintype "input"))
    )
    (net (code "20") (name "MOTOR2B") (class "Default")
      (node (ref "U1") (pin "32") (pinfunction "PA23_32") (pintype "bidirectional"))
      (node (ref "U6") (pin "2") (pinfunction "IN2_2") (pintype "input"))
    )
    (net (code "21") (name "NEOPIXEL") (class "Default")
      (node (ref "U1") (pin "15") (pinfunction "PA10_15") (pintype "bidirectional"))
      (node (ref "U8") (pin "2") (pinfunction "I_2") (pintype "input"))
    )
    (net (code "22") (name "NEOPIXEL_INTERNAL") (class "Default")
      (node (ref "D2") (pin "2") (pinfunction "DI_2") (pintype "input"))
      (node (ref "U8") (pin "4") (pinfunction "O_4") (pintype "tri_state"))
    )
    (net (code "23") (name "NEOPIXEL_OUT") (class "Default")
      (node (ref "D2") (pin "4") (pinfunction "DO_4") (pintype "output"))
      (node (ref "J11") (pin "1") (pinfunction "1_1") (pintype "passive"))
      (node (ref "J15") (pin "2") (pinfunction "2_2") (pintype "passive"))
    )
    (net (code "24") (name "Net-(D1-Pad+)") (class "Default")
      (node (ref "D1") (pin "+") (pinfunction "+_+") (pintype "passive"))
      (node (ref "R4") (pin "1") (pinfunction "1_1") (pintype "passive"))
    )
    (net (code "25") (name "Net-(J14-Pad5)") (class "Default")
      (node (ref "J14") (pin "5") (pinfunction "5_5") (pintype "passive"))
      (node (ref "J14") (pin "6") (pinfunction "6_6") (pintype "passive"))
    )
    (net (code "26") (name "Net-(J14-Pad10)") (class "Default")
      (node (ref "J14") (pin "10") (pinfunction "10_10") (pintype "passive"))
      (node (ref "J14") (pin "9") (pinfunction "9_9") (pintype "passive"))
    )
    (net (code "27") (name "Net-(J14-Pad11)") (class "Default")
      (node (ref "J14") (pin "11") (pinfunction "11_11") (pintype "passive"))
      (node (ref "J14") (pin "12") (pinfunction "12_12") (pintype "passive"))
    )
    (net (code "28") (name "Net-(J14-Pad13)") (class "Default")
      (node (ref "J14") (pin "13") (pinfunction "13_13") (pintype "passive"))
      (node (ref "J14") (pin "14") (pinfunction "14_14") (pintype "passive"))
    )
    (net (code "29") (name "Net-(J14-Pad15)") (class "Default")
      (node (ref "J14") (pin "15") (pinfunction "15_15") (pintype "passive"))
      (node (ref "J14") (pin "16") (pinfunction "16_16") (pintype "passive"))
    )
    (net (code "30") (name "Net-(J14-Pad17)") (class "Default")
      (node (ref "J14") (pin "17") (pinfunction "17_17") (pintype "passive"))
      (node (ref "J14") (pin "18") (pinfunction "18_18") (pintype "passive"))
    )
    (net (code "31") (name "Net-(J14-Pad19)") (class "Default")
      (node (ref "J14") (pin "19") (pinfunction "19_19") (pintype "passive"))
      (node (ref "J14") (pin "20") (pinfunction "20_20") (pintype "passive"))
    )
    (net (code "32") (name "Net-(J14-Pad21)") (class "Default")
      (node (ref "J14") (pin "21") (pinfunction "21_21") (pintype "passive"))
      (node (ref "J14") (pin "22") (pinfunction "22_22") (pintype "passive"))
    )
    (net (code "33") (name "Net-(J14-Pad23)") (class "Default")
      (node (ref "J14") (pin "23") (pinfunction "23_23") (pintype "passive"))
      (node (ref "J14") (pin "24") (pinfunction "24_24") (pintype "passive"))
    )
    (net (code "34") (name "Net-(J14-Pad25)") (class "Default")
      (node (ref "J14") (pin "25") (pinfunction "25_25") (pintype "passive"))
      (node (ref "J14") (pin "26") (pinfunction "26_26") (pintype "passive"))
    )
    (net (code "35") (name "Net-(J14-Pad27)") (class "Default")
      (node (ref "J14") (pin "27") (pinfunction "27_27") (pintype "passive"))
      (node (ref "J14") (pin "28") (pinfunction "28_28") (pintype "passive"))
    )
    (net (code "36") (name "Net-(J14-Pad29)") (class "Default")
      (node (ref "J14") (pin "29") (pinfunction "29_29") (pintype "passive"))
      (node (ref "J14") (pin "30") (pinfunction "30_30") (pintype "passive"))
    )
    (net (code "37") (name "Net-(J14-Pad31)") (class "Default")
      (node (ref "J14") (pin "31") (pinfunction "31_31") (pintype "passive"))
      (node (ref "J14") (pin "32") (pinfunction "32_32") (pintype "passive"))
    )
    (net (code "38") (name "Net-(J15-Pad3)") (class "Default")
      (node (ref "J15") (pin "3") (pinfunction "3_3") (pintype "passive"))
      (node (ref "J15") (pin "4") (pinfunction "4_4") (pintype "passive"))
    )
    (net (code "39") (name "Net-(J15-Pad7)") (class "Default")
      (node (ref "J15") (pin "7") (pinfunction "7_7") (pintype "passive"))
      (node (ref "J15") (pin "8") (pinfunction "8_8") (pintype "passive"))
    )
    (net (code "40") (name "Net-(J15-Pad10)") (class "Default")
      (node (ref "J15") (pin "10") (pinfunction "10_10") (pintype "passive"))
      (node (ref "J15") (pin "9") (pinfunction "9_9") (pintype "passive"))
    )
    (net (code "41") (name "Net-(J15-Pad11)") (class "Default")
      (node (ref "J15") (pin "11") (pinfunction "11_11") (pintype "passive"))
      (node (ref "J15") (pin "12") (pinfunction "12_12") (pintype "passive"))
    )
    (net (code "42") (name "Net-(J15-Pad13)") (class "Default")
      (node (ref "J15") (pin "13") (pinfunction "13_13") (pintype "passive"))
      (node (ref "J15") (pin "14") (pinfunction "14_14") (pintype "passive"))
    )
    (net (code "43") (name "Net-(J15-Pad15)") (class "Default")
      (node (ref "J15") (pin "15") (pinfunction "15_15") (pintype "passive"))
      (node (ref "J15") (pin "16") (pinfunction "16_16") (pintype "passive"))
    )
    (net (code "44") (name "Net-(J15-Pad17)") (class "Default")
      (node (ref "J15") (pin "17") (pinfunction "17_17") (pintype "passive"))
      (node (ref "J15") (pin "18") (pinfunction "18_18") (pintype "passive"))
    )
    (net (code "45") (name "Net-(J15-Pad19)") (class "Default")
      (node (ref "J15") (pin "19") (pinfunction "19_19") (pintype "passive"))
      (node (ref "J15") (pin "20") (pinfunction "20_20") (pintype "passive"))
    )
    (net (code "46") (name "Net-(R10-Pad1)") (class "Default")
      (node (ref "R10") (pin "1") (pinfunction "1_1") (pintype "passive"))
      (node (ref "SW1") (pin "1") (pinfunction "P1_1") (pintype "passive"))
      (node (ref "SW1") (pin "4") (pinfunction "P1_4") (pintype "passive"))
    )
    (net (code "47") (name "Net-(U1-VDDANA)") (class "Default")
      (node (ref "C12") (pin "2") (pinfunction "2_2") (pintype "passive"))
      (node (ref "FB") (pin "1") (pinfunction "1_1") (pintype "passive"))
      (node (ref "U1") (pin "6") (pinfunction "VDDANA_6") (pintype "power_in"))
    )
    (net (code "48") (name "Net-(U1-VDDCORE)") (class "Default")
      (node (ref "C10") (pin "2") (pinfunction "2_2") (pintype "passive"))
      (node (ref "U1") (pin "43") (pinfunction "VDDCORE_43") (pintype "power_in"))
    )
    (net (code "49") (name "Net-(U2-BST)") (class "Default")
      (node (ref "C4") (pin "1") (pinfunction "1_1") (pintype "passive"))
      (node (ref "U2") (pin "5") (pinfunction "BST_5") (pintype "bidirectional"))
    )
    (net (code "50") (name "Net-(U2-EN{slash}SYNC)") (class "Default")
      (node (ref "R1") (pin "1") (pinfunction "1_1") (pintype "passive"))
      (node (ref "U2") (pin "6") (pinfunction "EN/SYNC_6") (pintype "bidirectional"))
    )
    (net (code "51") (name "Net-(U2-FB)") (class "Default")
      (node (ref "C5") (pin "1") (pinfunction "1_1") (pintype "passive"))
      (node (ref "R2") (pin "2") (pinfunction "2_2") (pintype "passive"))
      (node (ref "R3") (pin "1") (pinfunction "1_1") (pintype "passive"))
      (node (ref "U2") (pin "8") (pinfunction "FB_8") (pintype "bidirectional"))
    )
    (net (code "52") (name "Net-(U2-SW)") (class "Default")
      (node (ref "C4") (pin "2") (pinfunction "2_2") (pintype "passive"))
      (node (ref "L1") (pin "1") (pinfunction "1_1") (pintype "passive"))
      (node (ref "U2") (pin "3") (pinfunction "SW_3") (pintype "bidirectional"))
    )
    (net (code "53") (name "Net-(U2-VCC)") (class "Default")
      (node (ref "C3") (pin "2") (pinfunction "2_2") (pintype "passive"))
      (node (ref "U2") (pin "7") (pinfunction "VCC_7") (pintype "bidirectional"))
    )
    (net (code "54") (name "Net-(U5-ILIM)") (class "Default")
      (node (ref "R7") (pin "1") (pinfunction "1_1") (pintype "passive"))
      (node (ref "U5") (pin "4") (pinfunction "ILIM_4") (pintype "input"))
    )
    (net (code "55") (name "Net-(U5-OUT1)") (class "Default")
      (node (ref "J2") (pin "1") (pinfunction "1_1") (pintype "passive"))
      (node (ref "U5") (pin "6") (pinfunction "OUT1_6") (pintype "output"))
    )
    (net (code "56") (name "Net-(U5-OUT2)") (class "Default")
      (node (ref "J2") (pin "2") (pinfunction "2_2") (pintype "passive"))
      (node (ref "U5") (pin "8") (pinfunction "OUT2_8") (pintype "output"))
    )
    (net (code "57") (name "Net-(U6-ILIM)") (class "Default")
      (node (ref "R8") (pin "1") (pinfunction "1_1") (pintype "passive"))
      (node (ref "U6") (pin "4") (pinfunction "ILIM_4") (pintype "input"))
    )
    (net (code "58") (name "Net-(U6-OUT1)") (class "Default")
      (node (ref "J3") (pin "1") (pinfunction "1_1") (pintype "passive"))
      (node (ref "U6") (pin "6") (pinfunction "OUT1_6") (pintype "output"))
    )
    (net (code "59") (name "Net-(U6-OUT2)") (class "Default")
      (node (ref "J3") (pin "2") (pinfunction "2_2") (pintype "passive"))
      (node (ref "U6") (pin "8") (pinfunction "OUT2_8") (pintype "output"))
    )
    (net (code "60") (name "Net-(U7-B2)") (class "Default")
      (node (ref "J8") (pin "1") (pinfunction "1_1") (pintype "passive"))
      (node (ref "U7") (pin "12") (pinfunction "B2_12") (pintype "bidirectional"))
    )
    (net (code "61") (name "Net-(U7-B3)") (class "Default")
      (node (ref "J9") (pin "1") (pinfunction "1_1") (pintype "passive"))
      (node (ref "U7") (pin "11") (pinfunction "B3_11") (pintype "bidirectional"))
    )
    (net (code "62") (name "Net-(U7-B4)") (class "Default")
      (node (ref "J10") (pin "1") (pinfunction "1_1") (pintype "passive"))
      (node (ref "U7") (pin "10") (pinfunction "B4_10") (pintype "bidirectional"))
    )
    (net (code "63") (name "RX") (class "Default")
      (node (ref "J17") (pin "P$3") (pinfunction "3_P$3") (pintype "passive"))
      (node (ref "U1") (pin "20") (pinfunction "PB11_20") (pintype "bidirectional"))
    )
    (net (code "64") (name "SCL1") (class "Default")
      (node (ref "J15") (pin "21") (pinfunction "21_21") (pintype "passive"))
      (node (ref "J15") (pin "22") (pinfunction "22_22") (pintype "passive"))
      (node (ref "J6") (pin "1") (pinfunction "1_1") (pintype "passive"))
      (node (ref "R13") (pin "2") (pinfunction "2_2") (pintype "passive"))
      (node (ref "U1") (pin "26") (pinfunction "PA17_26") (pintype "bidirectional"))
    )
    (net (code "65") (name "SCL2") (class "Default")
      (node (ref "J16") (pin "P$2") (pinfunction "2_P$2") (pintype "passive"))
      (node (ref "R15") (pin "2") (pinfunction "2_2") (pintype "passive"))
      (node (ref "U1") (pin "22") (pinfunction "PA13_22") (pintype "bidirectional"))
      (node (ref "U9") (pin "13") (pinfunction "AP_SCL/AP_SCLK_13") (pintype "input"))
    )
    (net (code "66") (name "SDA1") (class "Default")
      (node (ref "J15") (pin "23") (pinfunction "23_23") (pintype "passive"))
      (node (ref "J15") (pin "24") (pinfunction "24_24") (pintype "passive"))
      (node (ref "J6") (pin "2") (pinfunction "2_2") (pintype "passive"))
      (node (ref "R14") (pin "2") (pinfunction "2_2") (pintype "passive"))
      (node (ref "U1") (pin "25") (pinfunction "PA16_25") (pintype "bidirectional"))
    )
    (net (code "67") (name "SDA2") (class "Default")
      (node (ref "J16") (pin "P$3") (pinfunction "3_P$3") (pintype "passive"))
      (node (ref "R16") (pin "2") (pinfunction "2_2") (pintype "passive"))
      (node (ref "U1") (pin "21") (pinfunction "PA12_21") (pintype "bidirectional"))
      (node (ref "U9") (pin "14") (pinfunction "AP_SDA/AP_SDIO/AP_SDI_14") (pintype "bidirectional"))
    )
    (net (code "68") (name "SERVO1") (class "Default")
      (node (ref "J12") (pin "3") (pinfunction "3_3") (pintype "passive"))
      (node (ref "U1") (pin "1") (pinfunction "PA00_1") (pintype "bidirectional"))
    )
    (net (code "69") (name "SERVO2") (class "Default")
      (node (ref "J12") (pin "6") (pinfunction "6_6") (pintype "passive"))
      (node (ref "U1") (pin "2") (pinfunction "PA01_2") (pintype "bidirectional"))
    )
    (net (code "70") (name "SERVO3") (class "Default")
      (node (ref "J12") (pin "9") (pinfunction "9_9") (pintype "passive"))
      (node (ref "U1") (pin "13") (pinfunction "PA08_13") (pintype "bidirectional"))
    )
    (net (code "71") (name "SERVO4") (class "Default")
      (node (ref "J12") (pin "12") (pinfunction "12_12") (pintype "passive"))
      (node (ref "U1") (pin "14") (pinfunction "PA09_14") (pintype "bidirectional"))
    )
    (net (code "72") (name "SONAR1ECHO") (class "Default")
      (node (ref "U1") (pin "41") (pinfunction "PA28_41") (pintype "bidirectional"))
      (node (ref "U7") (pin "5") (pinfunction "A4_5") (pintype "bidirectional"))
    )
    (net (code "73") (name "SONAR1TRIG") (class "Default")
      (node (ref "J10") (pin "2") (pinfunction "2_2") (pintype "passive"))
      (node (ref "U1") (pin "39") (pinfunction "PA27_39") (pintype "bidirectional"))
    )
    (net (code "74") (name "SONAR2ECHO") (class "Default")
      (node (ref "U1") (pin "47") (pinfunction "PB02_47") (pintype "bidirectional"))
      (node (ref "U7") (pin "4") (pinfunction "A3_4") (pintype "bidirectional"))
    )
    (net (code "75") (name "SONAR2TRIG") (class "Default")
      (node (ref "J9") (pin "2") (pinfunction "2_2") (pintype "passive"))
      (node (ref "U1") (pin "38") (pinfunction "PB23_38") (pintype "bidirectional"))
    )
    (net (code "76") (name "SONAR3ECHO") (class "Default")
      (node (ref "U1") (pin "48") (pinfunction "PB03_48") (pintype "bidirectional"))
      (node (ref "U7") (pin "3") (pinfunction "A2_3") (pintype "bidirectional"))
    )
    (net (code "77") (name "SONAR3TRIG") (class "Default")
      (node (ref "J8") (pin "2") (pinfunction "2_2") (pintype "passive"))
      (node (ref "U1") (pin "37") (pinfunction "PB22_37") (pintype "bidirectional"))
    )
    (net (code "78") (name "SWCLK") (class "Default")
      (node (ref "R11") (pin "2") (pinfunction "2_2") (pintype "passive"))
      (node (ref "TP2") (pin "TP") (pinfunction "TP_TP") (pintype "input"))
      (node (ref "U1") (pin "45") (pinfunction "PA30_45") (pintype "bidirectional"))
    )
    (net (code "79") (name "SWDIO") (class "Default")
      (node (ref "TP3") (pin "TP") (pinfunction "TP_TP") (pintype "input"))
      (node (ref "U1") (pin "46") (pinfunction "PA31_46") (pintype "bidirectional"))
    )
    (net (code "80") (name "TX") (class "Default")
      (node (ref "J17") (pin "P$2") (pinfunction "2_P$2") (pintype "passive"))
      (node (ref "U1") (pin "19") (pinfunction "PB10_19") (pintype "bidirectional"))
    )
    (net (code "81") (name "VSENSE") (class "Default")
      (node (ref "R5") (pin "1") (pinfunction "1_1") (pintype "passive"))
      (node (ref "R6") (pin "1") (pinfunction "1_1") (pintype "passive"))
      (node (ref "U1") (pin "12") (pinfunction "PA07_12") (pintype "bidirectional"))
    )
    (net (code "82") (name "unconnected-(J15-Pad1)") (class "Default")
      (node (ref "J15") (pin "1") (pinfunction "1_1") (pintype "passive"))
    )
    (net (code "83") (name "unconnected-(J15-Pad5)") (class "Default")
      (node (ref "J15") (pin "5") (pinfunction "5_5") (pintype "passive"))
    )
    (net (code "84") (name "unconnected-(J17-4-PadP$4)") (class "Default")
      (node (ref "J17") (pin "P$4") (pinfunction "4_P$4") (pintype "passive"))
    )
    (net (code "85") (name "unconnected-(J17-5-PadP$5)") (class "Default")
      (node (ref "J17") (pin "P$5") (pinfunction "5_P$5") (pintype "passive"))
    )
    (net (code "86") (name "unconnected-(U1-PA03-Pad4)") (class "Default")
      (node (ref "U1") (pin "4") (pinfunction "PA03_4") (pintype "bidirectional"))
    )
    (net (code "87") (name "unconnected-(U1-PA11-Pad16)") (class "Default")
      (node (ref "U1") (pin "16") (pinfunction "PA11_16") (pintype "bidirectional"))
    )
    (net (code "88") (name "unconnected-(U7-A1-Pad2)") (class "Default")
      (node (ref "U7") (pin "2") (pinfunction "A1_2") (pintype "bidirectional"))
    )
    (net (code "89") (name "unconnected-(U7-B1-Pad13)") (class "Default")
      (node (ref "U7") (pin "13") (pinfunction "B1_13") (pintype "bidirectional"))
    )
    (net (code "90") (name "unconnected-(U7-NC-Pad9)") (class "Default")
      (node (ref "U7") (pin "9") (pinfunction "NC_9") (pintype "no_connect"))
    )
    (net (code "91") (name "unconnected-(U7-NC_2-Pad6)") (class "Default")
      (node (ref "U7") (pin "6") (pinfunction "NC_2_6") (pintype "no_connect"))
    )
    (net (code "92") (name "unconnected-(U9-INT1{slash}INT-Pad4)") (class "Default")
      (node (ref "U9") (pin "4") (pinfunction "INT1/INT_4") (pintype "output"))
    )
    (net (code "93") (name "unconnected-(U9-RESV_1-Pad2)") (class "Default")
      (node (ref "U9") (pin "2") (pinfunction "RESV_1_2") (pintype "bidirectional"))
    )
    (net (code "94") (name "unconnected-(U9-RESV_2-Pad3)") (class "Default")
      (node (ref "U9") (pin "3") (pinfunction "RESV_2_3") (pintype "bidirectional"))
    )
    (net (code "95") (name "unconnected-(U9-RESV_4-Pad10)") (class "Default")
      (node (ref "U9") (pin "10") (pinfunction "RESV_4_10") (pintype "bidirectional"))
    )
    (net (code "96") (name "unconnected-(U9-RESV_5-Pad11)") (class "Default")
      (node (ref "U9") (pin "11") (pinfunction "RESV_5_11") (pintype "bidirectional"))
    )
    (net (code "97") (name "unconnected-(USB1-ID-Pad4)") (class "Default")
      (node (ref "USB1") (pin "4") (pinfunction "ID_4") (pintype "bidirectional"))
    )
    (net (code "98") (name "unconnected-(USB1-VCC-Pad1)") (class "Default")
      (node (ref "USB1") (pin "1") (pinfunction "VCC_1") (pintype "bidirectional"))
    )
    (net (code "99") (name "~{RESET}") (class "Default")
      (node (ref "C14") (pin "1") (pinfunction "1_1") (pintype "passive"))
      (node (ref "J14") (pin "1") (pinfunction "1_1") (pintype "passive"))
      (node (ref "J14") (pin "2") (pinfunction "2_2") (pintype "passive"))
      (node (ref "R10") (pin "2") (pinfunction "2_2") (pintype "passive"))
      (node (ref "TP1") (pin "TP") (pinfunction "TP_TP") (pintype "input"))
      (node (ref "U1") (pin "40") (pinfunction "RSTN_40") (pintype "bidirectional"))
    )
  )
)
